# PIC_V_1.net
KiCad netlist of a schematic drawn in EAGLE
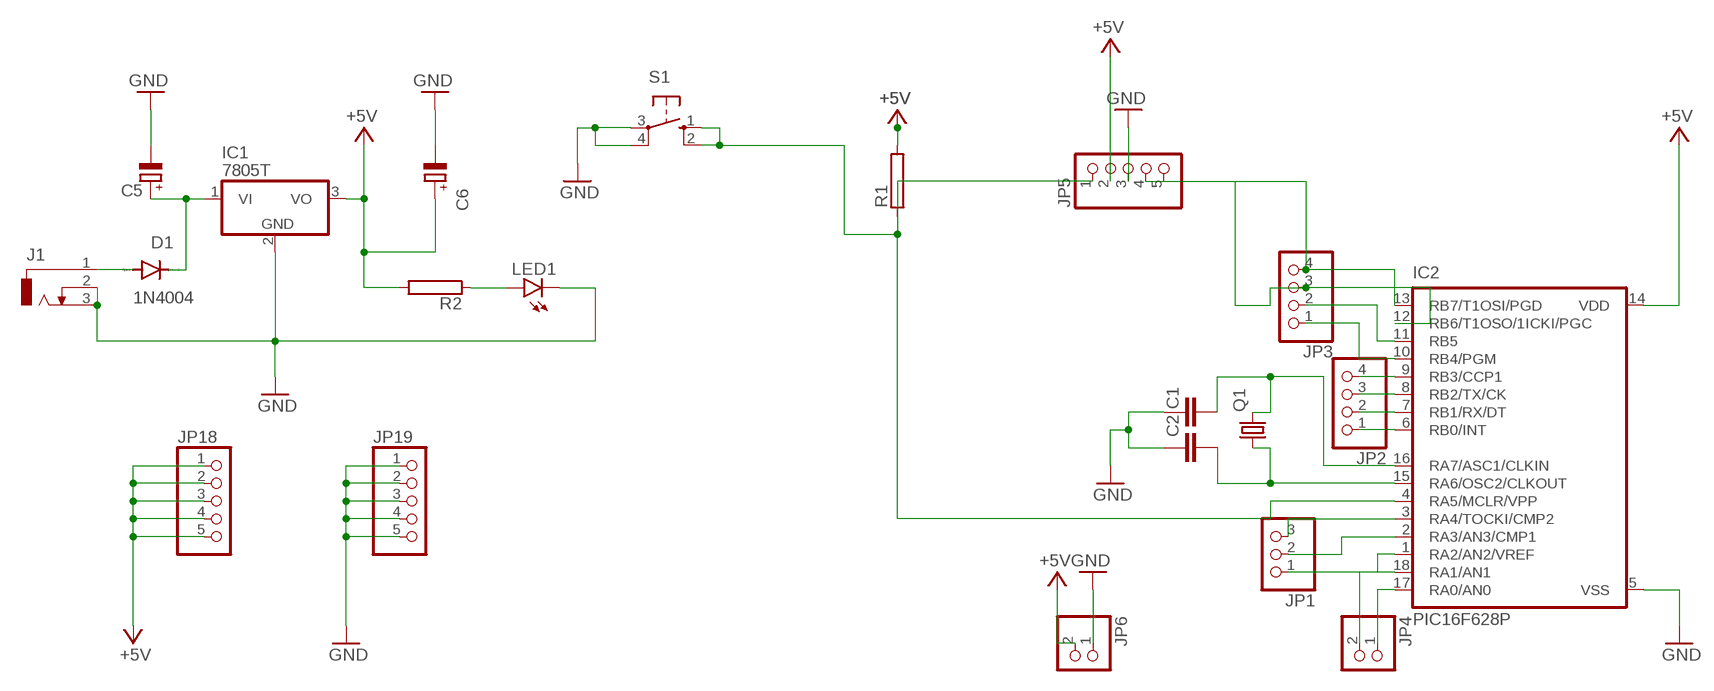
[diagram p0: schematic, sheet 1]

(export (version "E")
  (design (tool "Eeschema 10.0.6"))
  (components
    (comp (ref "C1")
      (value "C2.5/2")
      (footprint "eagle-import:C2.5-2")
      (libsource (lib "eagle-import") (part "C2.5/2"))
    )
    (comp (ref "C2")
      (value "C2.5/2")
      (footprint "eagle-import:C2.5-2")
      (libsource (lib "eagle-import") (part "C2.5/2"))
    )
    (comp (ref "C5")
      (value "CPOL-EUE2,5-6E")
      (footprint "eagle-import:E2,5-6E")
      (libsource (lib "eagle-import") (part "CPOL-EUE2,5-6E"))
    )
    (comp (ref "C6")
      (value "CPOL-EUE2,5-6E")
      (footprint "eagle-import:E2,5-6E")
      (libsource (lib "eagle-import") (part "CPOL-EUE2,5-6E"))
    )
    (comp (ref "D1")
      (value "1N4004")
      (footprint "eagle-import:DO41-10")
      (libsource (lib "eagle-import") (part "1N4004"))
    )
    (comp (ref "IC1")
      (value "7805T")
      (footprint "eagle-import:TO220H")
      (libsource (lib "eagle-import") (part "78T05"))
    )
    (comp (ref "IC2")
      (value "PIC16F628P")
      (footprint "eagle-import:DIL18")
      (fields (field (name "MF") "MICROCHIP") (field (name "MPN") "PIC16F628-20/P"))
      (libsource (lib "eagle-import") (part "PIC16F628P"))
    )
    (comp (ref "J1")
      (value "DCJ0303")
      (footprint "eagle-import:DCJ0303")
      (libsource (lib "eagle-import") (part "DCJ0303"))
    )
    (comp (ref "JP1")
      (value "PINHD-1X3")
      (footprint "eagle-import:1X03")
      (libsource (lib "eagle-import") (part "PINHD-1X3"))
    )
    (comp (ref "JP2")
      (value "PINHD-1X4")
      (footprint "eagle-import:1X04")
      (libsource (lib "eagle-import") (part "PINHD-1X4"))
    )
    (comp (ref "JP3")
      (value "PINHD-1X4")
      (footprint "eagle-import:1X04")
      (libsource (lib "eagle-import") (part "PINHD-1X4"))
    )
    (comp (ref "JP4")
      (value "PINHD-1X2")
      (footprint "eagle-import:1X02")
      (libsource (lib "eagle-import") (part "PINHD-1X2"))
    )
    (comp (ref "JP5")
      (value "PINHD-1X5")
      (footprint "eagle-import:1X05")
      (libsource (lib "eagle-import") (part "PINHD-1X5"))
    )
    (comp (ref "JP6")
      (value "PINHD-1X2")
      (footprint "eagle-import:1X02")
      (libsource (lib "eagle-import") (part "PINHD-1X2"))
    )
    (comp (ref "JP18")
      (value "PINHD-1X5")
      (footprint "eagle-import:1X05")
      (libsource (lib "eagle-import") (part "PINHD-1X5"))
    )
    (comp (ref "JP19")
      (value "PINHD-1X5")
      (footprint "eagle-import:1X05")
      (libsource (lib "eagle-import") (part "PINHD-1X5"))
    )
    (comp (ref "LED1")
      (value "LED5MM")
      (footprint "eagle-import:LED5MM")
      (libsource (lib "eagle-import") (part "LED5MM"))
    )
    (comp (ref "Q1")
      (value "CRYSTALHC49U-V")
      (footprint "eagle-import:HC49U-V")
      (libsource (lib "eagle-import") (part "CRYSTALHC49U-V"))
    )
    (comp (ref "R1")
      (value "RRS1/4")
      (footprint "eagle-import:RS1_4")
      (fields (field (name "MF") "OHMITE") (field (name "MPN") "RRS1K0"))
      (libsource (lib "eagle-import") (part "RRS1/4"))
    )
    (comp (ref "R2")
      (value "RRS1/4")
      (footprint "eagle-import:RS1_4")
      (fields (field (name "MF") "OHMITE") (field (name "MPN") "RRS1K0"))
      (libsource (lib "eagle-import") (part "RRS1/4"))
    )
    (comp (ref "S1")
      (value "10-XX")
      (footprint "eagle-import:B3F-10XX")
      (fields (field (name "MPN") "B3F-1000"))
      (libsource (lib "eagle-import") (part "10-XX"))
    )
  )
  (nets
    (net (code "1") (name "+5V") (class "Default")
      (node (ref "C6") (pin "+") (pinfunction "+_+") (pintype "passive"))
      (node (ref "IC1") (pin "3") (pinfunction "VO_3") (pintype "passive"))
      (node (ref "IC2") (pin "14") (pinfunction "VDD_14") (pintype "power_in"))
      (node (ref "JP18") (pin "1") (pinfunction "1_1") (pintype "passive"))
      (node (ref "JP18") (pin "2") (pinfunction "2_2") (pintype "passive"))
      (node (ref "JP18") (pin "3") (pinfunction "3_3") (pintype "passive"))
      (node (ref "JP18") (pin "4") (pinfunction "4_4") (pintype "passive"))
      (node (ref "JP18") (pin "5") (pinfunction "5_5") (pintype "passive"))
      (node (ref "JP5") (pin "2") (pinfunction "2_2") (pintype "passive"))
      (node (ref "JP6") (pin "2") (pinfunction "2_2") (pintype "passive"))
      (node (ref "R1") (pin "2") (pinfunction "2_2") (pintype "passive"))
      (node (ref "R2") (pin "2") (pinfunction "2_2") (pintype "passive"))
    )
    (net (code "2") (name "GND") (class "Default")
      (node (ref "C1") (pin "1") (pinfunction "1_1") (pintype "passive"))
      (node (ref "C2") (pin "1") (pinfunction "1_1") (pintype "passive"))
      (node (ref "C5") (pin "-") (pinfunction "-_-") (pintype "passive"))
      (node (ref "C6") (pin "-") (pinfunction "-_-") (pintype "passive"))
      (node (ref "IC1") (pin "2") (pinfunction "GND_2") (pintype "passive"))
      (node (ref "IC2") (pin "5") (pinfunction "VSS_5") (pintype "power_in"))
      (node (ref "J1") (pin "2") (pinfunction "2_2") (pintype "passive"))
      (node (ref "J1") (pin "3") (pinfunction "3_3") (pintype "passive"))
      (node (ref "JP19") (pin "1") (pinfunction "1_1") (pintype "passive"))
      (node (ref "JP19") (pin "2") (pinfunction "2_2") (pintype "passive"))
      (node (ref "JP19") (pin "3") (pinfunction "3_3") (pintype "passive"))
      (node (ref "JP19") (pin "4") (pinfunction "4_4") (pintype "passive"))
      (node (ref "JP19") (pin "5") (pinfunction "5_5") (pintype "passive"))
      (node (ref "JP5") (pin "3") (pinfunction "3_3") (pintype "passive"))
      (node (ref "JP6") (pin "1") (pinfunction "1_1") (pintype "passive"))
      (node (ref "LED1") (pin "K") (pinfunction "C_K") (pintype "passive"))
      (node (ref "S1") (pin "3") (pinfunction "P_3") (pintype "passive"))
      (node (ref "S1") (pin "4") (pinfunction "P1_4") (pintype "passive"))
    )
    (net (code "3") (name "Net-(D1-PadA)") (class "Default")
      (node (ref "D1") (pin "A") (pinfunction "A_A") (pintype "passive"))
      (node (ref "J1") (pin "1") (pinfunction "1_1") (pintype "passive"))
    )
    (net (code "4") (name "Net-(IC1-VI)") (class "Default")
      (node (ref "C5") (pin "+") (pinfunction "+_+") (pintype "passive"))
      (node (ref "D1") (pin "C") (pinfunction "C_C") (pintype "passive"))
      (node (ref "IC1") (pin "1") (pinfunction "VI_1") (pintype "input"))
    )
    (net (code "5") (name "Net-(IC2-RA0{slash}AN0)") (class "Default")
      (node (ref "IC2") (pin "17") (pinfunction "RA0/AN0_17") (pintype "bidirectional"))
      (node (ref "JP4") (pin "1") (pinfunction "1_1") (pintype "passive"))
    )
    (net (code "6") (name "Net-(IC2-RA1{slash}AN1)") (class "Default")
      (node (ref "IC2") (pin "18") (pinfunction "RA1/AN1_18") (pintype "bidirectional"))
      (node (ref "JP4") (pin "2") (pinfunction "2_2") (pintype "passive"))
    )
    (net (code "7") (name "Net-(IC2-RA2{slash}AN2{slash}VREF)") (class "Default")
      (node (ref "IC2") (pin "1") (pinfunction "RA2/AN2/VREF_1") (pintype "bidirectional"))
      (node (ref "JP1") (pin "1") (pinfunction "1_1") (pintype "passive"))
    )
    (net (code "8") (name "Net-(IC2-RA3{slash}AN3{slash}CMP1)") (class "Default")
      (node (ref "IC2") (pin "2") (pinfunction "RA3/AN3/CMP1_2") (pintype "bidirectional"))
      (node (ref "JP1") (pin "2") (pinfunction "2_2") (pintype "passive"))
    )
    (net (code "9") (name "Net-(IC2-RA4{slash}TOCKI{slash}CMP2)") (class "Default")
      (node (ref "IC2") (pin "3") (pinfunction "RA4/TOCKI/CMP2_3") (pintype "bidirectional"))
      (node (ref "JP1") (pin "3") (pinfunction "3_3") (pintype "passive"))
    )
    (net (code "10") (name "Net-(IC2-RA5{slash}MCLR{slash}VPP)") (class "Default")
      (node (ref "IC2") (pin "4") (pinfunction "RA5/MCLR/VPP_4") (pintype "input"))
      (node (ref "JP5") (pin "1") (pinfunction "1_1") (pintype "passive"))
      (node (ref "R1") (pin "1") (pinfunction "1_1") (pintype "passive"))
      (node (ref "S1") (pin "1") (pinfunction "S_1") (pintype "passive"))
      (node (ref "S1") (pin "2") (pinfunction "S1_2") (pintype "passive"))
    )
    (net (code "11") (name "Net-(IC2-RA6{slash}OSC2{slash}CLKOUT)") (class "Default")
      (node (ref "C2") (pin "2") (pinfunction "2_2") (pintype "passive"))
      (node (ref "IC2") (pin "15") (pinfunction "RA6/OSC2/CLKOUT_15") (pintype "bidirectional"))
      (node (ref "Q1") (pin "1") (pinfunction "1_1") (pintype "passive"))
    )
    (net (code "12") (name "Net-(IC2-RA7{slash}ASC1{slash}CLKIN)") (class "Default")
      (node (ref "C1") (pin "2") (pinfunction "2_2") (pintype "passive"))
      (node (ref "IC2") (pin "16") (pinfunction "RA7/ASC1/CLKIN_16") (pintype "bidirectional"))
      (node (ref "Q1") (pin "2") (pinfunction "2_2") (pintype "passive"))
    )
    (net (code "13") (name "Net-(IC2-RB0{slash}INT)") (class "Default")
      (node (ref "IC2") (pin "6") (pinfunction "RB0/INT_6") (pintype "bidirectional"))
      (node (ref "JP2") (pin "1") (pinfunction "1_1") (pintype "passive"))
    )
    (net (code "14") (name "Net-(IC2-RB1{slash}RX{slash}DT)") (class "Default")
      (node (ref "IC2") (pin "7") (pinfunction "RB1/RX/DT_7") (pintype "bidirectional"))
      (node (ref "JP2") (pin "2") (pinfunction "2_2") (pintype "passive"))
    )
    (net (code "15") (name "Net-(IC2-RB2{slash}TX{slash}CK)") (class "Default")
      (node (ref "IC2") (pin "8") (pinfunction "RB2/TX/CK_8") (pintype "bidirectional"))
      (node (ref "JP2") (pin "3") (pinfunction "3_3") (pintype "passive"))
    )
    (net (code "16") (name "Net-(IC2-RB3{slash}CCP1)") (class "Default")
      (node (ref "IC2") (pin "9") (pinfunction "RB3/CCP1_9") (pintype "bidirectional"))
      (node (ref "JP2") (pin "4") (pinfunction "4_4") (pintype "passive"))
    )
    (net (code "17") (name "Net-(IC2-RB4{slash}PGM)") (class "Default")
      (node (ref "IC2") (pin "10") (pinfunction "RB4/PGM_10") (pintype "bidirectional"))
      (node (ref "JP3") (pin "1") (pinfunction "1_1") (pintype "passive"))
    )
    (net (code "18") (name "Net-(IC2-RB5)") (class "Default")
      (node (ref "IC2") (pin "11") (pinfunction "RB5_11") (pintype "bidirectional"))
      (node (ref "JP3") (pin "2") (pinfunction "2_2") (pintype "passive"))
    )
    (net (code "19") (name "Net-(IC2-RB6{slash}T1OSO{slash}1ICKI{slash}PGC)") (class "Default")
      (node (ref "IC2") (pin "12") (pinfunction "RB6/T1OSO/1ICKI/PGC_12") (pintype "bidirectional"))
      (node (ref "JP3") (pin "3") (pinfunction "3_3") (pintype "passive"))
      (node (ref "JP5") (pin "5") (pinfunction "5_5") (pintype "passive"))
    )
    (net (code "20") (name "Net-(IC2-RB7{slash}T1OSI{slash}PGD)") (class "Default")
      (node (ref "IC2") (pin "13") (pinfunction "RB7/T1OSI/PGD_13") (pintype "bidirectional"))
      (node (ref "JP3") (pin "4") (pinfunction "4_4") (pintype "passive"))
      (node (ref "JP5") (pin "4") (pinfunction "4_4") (pintype "passive"))
    )
    (net (code "21") (name "Net-(LED1-PadA)") (class "Default")
      (node (ref "LED1") (pin "A") (pinfunction "A_A") (pintype "passive"))
      (node (ref "R2") (pin "1") (pinfunction "1_1") (pintype "passive"))
    )
  )
)
